# Grove_-_FM_Receiver_v1_0.net
KiCad netlist of a schematic drawn in EAGLE
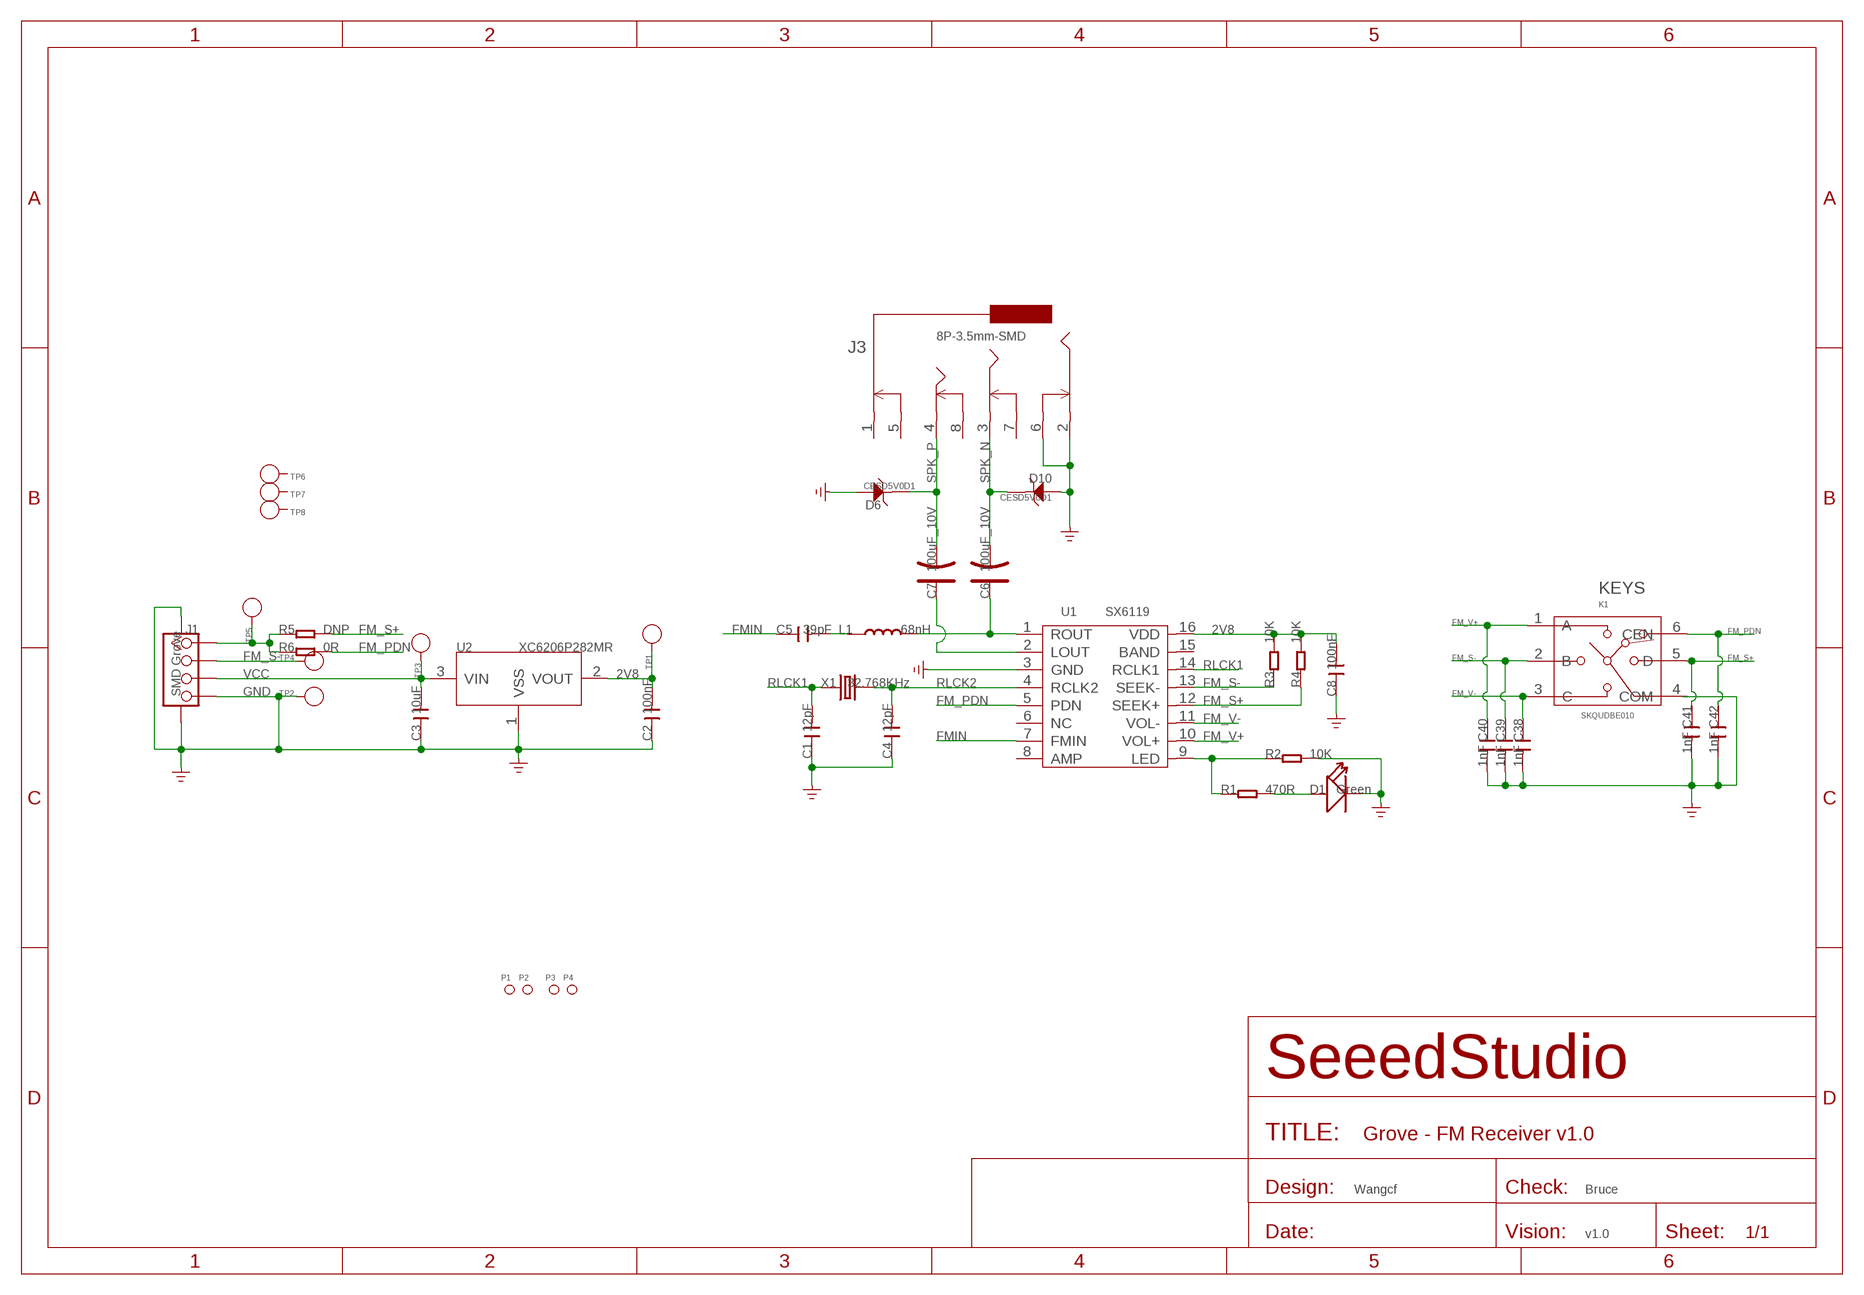
[diagram p0: schematic, sheet 1]

(export (version "E")
  (design (tool "Eeschema 10.0.6"))
  (components
    (comp (ref "C1")
      (value "12pF")
      (footprint "eagle-import:C0603")
      (libsource (lib "eagle-import") (part "C-0603"))
    )
    (comp (ref "C2")
      (value "100nF")
      (footprint "eagle-import:C0603")
      (libsource (lib "eagle-import") (part "C-0603"))
    )
    (comp (ref "C3")
      (value "10uF")
      (footprint "eagle-import:C0805")
      (libsource (lib "eagle-import") (part "C-0805"))
    )
    (comp (ref "C4")
      (value "12pF")
      (footprint "eagle-import:C0603")
      (libsource (lib "eagle-import") (part "C-0603"))
    )
    (comp (ref "C5")
      (value "39pF")
      (footprint "eagle-import:C0603")
      (libsource (lib "eagle-import") (part "C-0603"))
    )
    (comp (ref "C6")
      (value "100uF_10V")
      (footprint "eagle-import:AVX-B")
      (libsource (lib "eagle-import") (part "CAP-AVX-B"))
    )
    (comp (ref "C7")
      (value "100uF_10V")
      (footprint "eagle-import:AVX-B")
      (libsource (lib "eagle-import") (part "CAP-AVX-B"))
    )
    (comp (ref "C8")
      (value "100nF")
      (footprint "eagle-import:C0603")
      (libsource (lib "eagle-import") (part "C-0603"))
    )
    (comp (ref "C38")
      (value "1nF")
      (footprint "eagle-import:C0603")
      (libsource (lib "eagle-import") (part "C-0603"))
    )
    (comp (ref "C39")
      (value "1nF")
      (footprint "eagle-import:C0603")
      (libsource (lib "eagle-import") (part "C-0603"))
    )
    (comp (ref "C40")
      (value "1nF")
      (footprint "eagle-import:C0603")
      (libsource (lib "eagle-import") (part "C-0603"))
    )
    (comp (ref "C41")
      (value "1nF")
      (footprint "eagle-import:C0603")
      (libsource (lib "eagle-import") (part "C-0603"))
    )
    (comp (ref "C42")
      (value "1nF")
      (footprint "eagle-import:C0603")
      (libsource (lib "eagle-import") (part "C-0603"))
    )
    (comp (ref "D1")
      (value "Green")
      (footprint "eagle-import:LED-0603")
      (libsource (lib "eagle-import") (part "LED'0603'"))
    )
    (comp (ref "D6")
      (value "CESD5V0D1")
      (footprint "eagle-import:SOD123-2.7X1.6")
      (libsource (lib "eagle-import") (part "D-ESD"))
    )
    (comp (ref "D10")
      (value "CESD5V0D1")
      (footprint "eagle-import:SOD123-2.7X1.6")
      (libsource (lib "eagle-import") (part "D-ESD"))
    )
    (comp (ref "J1")
      (value "SMD Grove")
      (footprint "eagle-import:4P-SMD-2.0")
      (libsource (lib "eagle-import") (part "TWIG-4P-2.0-SMD-FEMALE-REINFORCE'DD'"))
    )
    (comp (ref "J3")
      (value "8P-3.5mm-SMD")
      (footprint "eagle-import:8P-3.5-SMD")
      (libsource (lib "eagle-import") (part "AUDIO-8P'PJ-3536-L6S'"))
    )
    (comp (ref "K1")
      (value "SKQUDBE010")
      (footprint "eagle-import:6P-10X10X8.6MM")
      (libsource (lib "eagle-import") (part "SKQUDBE010"))
    )
    (comp (ref "L1")
      (value "68nH")
      (footprint "eagle-import:L0603")
      (libsource (lib "eagle-import") (part "L'0603'"))
    )
    (comp (ref "P1")
      (value "PAD-MARK")
      (footprint "eagle-import:ROUND-MARK-1.0")
      (fields (field (name "PARTNO") "DNP"))
      (libsource (lib "eagle-import") (part "PAD-MARK"))
    )
    (comp (ref "P2")
      (value "PAD-MARK")
      (footprint "eagle-import:ROUND-MARK-1.0")
      (fields (field (name "PARTNO") "DNP"))
      (libsource (lib "eagle-import") (part "PAD-MARK"))
    )
    (comp (ref "P3")
      (value "PAD-MARK")
      (footprint "eagle-import:ROUND-MARK-1.0")
      (fields (field (name "PARTNO") "DNP"))
      (libsource (lib "eagle-import") (part "PAD-MARK"))
    )
    (comp (ref "P4")
      (value "PAD-MARK")
      (footprint "eagle-import:ROUND-MARK-1.0")
      (fields (field (name "PARTNO") "DNP"))
      (libsource (lib "eagle-import") (part "PAD-MARK"))
    )
    (comp (ref "R1")
      (value "470R")
      (footprint "eagle-import:R0603")
      (libsource (lib "eagle-import") (part "R-0603"))
    )
    (comp (ref "R2")
      (value "10K")
      (footprint "eagle-import:R0603")
      (libsource (lib "eagle-import") (part "R-0603"))
    )
    (comp (ref "R3")
      (value "10K")
      (footprint "eagle-import:R0603")
      (libsource (lib "eagle-import") (part "R-0603"))
    )
    (comp (ref "R4")
      (value "10K")
      (footprint "eagle-import:R0603")
      (libsource (lib "eagle-import") (part "R-0603"))
    )
    (comp (ref "R5")
      (value "DNP")
      (footprint "eagle-import:R0603")
      (libsource (lib "eagle-import") (part "R-0603"))
    )
    (comp (ref "R6")
      (value "0R")
      (footprint "eagle-import:R0603")
      (libsource (lib "eagle-import") (part "R-0603"))
    )
    (comp (ref "TP1")
      (value "PAD-TEST-POINT'4545'")
      (footprint "eagle-import:TP_4545")
      (fields (field (name "PARTNO") "DNP"))
      (libsource (lib "eagle-import") (part "PAD-TEST-POINT'4545'"))
    )
    (comp (ref "TP2")
      (value "PAD-TEST-POINT'4545'")
      (footprint "eagle-import:TP_4545")
      (fields (field (name "PARTNO") "DNP"))
      (libsource (lib "eagle-import") (part "PAD-TEST-POINT'4545'"))
    )
    (comp (ref "TP3")
      (value "PAD-TEST-POINT'4545'")
      (footprint "eagle-import:TP_4545")
      (fields (field (name "PARTNO") "DNP"))
      (libsource (lib "eagle-import") (part "PAD-TEST-POINT'4545'"))
    )
    (comp (ref "TP4")
      (value "PAD-TEST-POINT'4545'")
      (footprint "eagle-import:TP_4545")
      (fields (field (name "PARTNO") "DNP"))
      (libsource (lib "eagle-import") (part "PAD-TEST-POINT'4545'"))
    )
    (comp (ref "TP5")
      (value "PAD-TEST-POINT'4545'")
      (footprint "eagle-import:TP_4545")
      (fields (field (name "PARTNO") "DNP"))
      (libsource (lib "eagle-import") (part "PAD-TEST-POINT'4545'"))
    )
    (comp (ref "TP6")
      (value "PAD-TEST-POINT'4545'")
      (footprint "eagle-import:TP_4545")
      (fields (field (name "PARTNO") "DNP"))
      (libsource (lib "eagle-import") (part "PAD-TEST-POINT'4545'"))
    )
    (comp (ref "TP7")
      (value "PAD-TEST-POINT'4545'")
      (footprint "eagle-import:TP_4545")
      (fields (field (name "PARTNO") "DNP"))
      (libsource (lib "eagle-import") (part "PAD-TEST-POINT'4545'"))
    )
    (comp (ref "TP8")
      (value "PAD-TEST-POINT'4545'")
      (footprint "eagle-import:TP_4545")
      (fields (field (name "PARTNO") "DNP"))
      (libsource (lib "eagle-import") (part "PAD-TEST-POINT'4545'"))
    )
    (comp (ref "U1")
      (value "SX6119")
      (footprint "eagle-import:SOP16")
      (libsource (lib "eagle-import") (part "SX6119"))
    )
    (comp (ref "U2")
      (value "XC6206P282MR")
      (footprint "eagle-import:SOT23")
      (libsource (lib "eagle-import") (part "XC6206MR"))
    )
    (comp (ref "X1")
      (value "32.768KHz")
      (footprint "eagle-import:2P-SMD-3.2X1.5")
      (libsource (lib "eagle-import") (part "CRYSTAL-3215"))
    )
  )
  (nets
    (net (code "1") (name "/2V8") (class "Default")
      (node (ref "C2") (pin "2") (pinfunction "2_2") (pintype "passive"))
      (node (ref "C8") (pin "2") (pinfunction "2_2") (pintype "passive"))
      (node (ref "R3") (pin "2") (pinfunction "2_2") (pintype "passive"))
      (node (ref "R4") (pin "2") (pinfunction "2_2") (pintype "passive"))
      (node (ref "TP1") (pin "T") (pinfunction "T_T") (pintype "bidirectional"))
      (node (ref "U1") (pin "16") (pinfunction "VDD_16") (pintype "bidirectional"))
      (node (ref "U2") (pin "2") (pinfunction "VOUT_2") (pintype "output"))
    )
    (net (code "2") (name "/FMIN") (class "Default")
      (node (ref "C5") (pin "1") (pinfunction "1_1") (pintype "passive"))
      (node (ref "U1") (pin "7") (pinfunction "FMIN_7") (pintype "bidirectional"))
    )
    (net (code "3") (name "/FM_PDN") (class "Default")
      (node (ref "C42") (pin "1") (pinfunction "1_1") (pintype "passive"))
      (node (ref "K1") (pin "6") (pinfunction "CEN_6") (pintype "bidirectional"))
      (node (ref "R6") (pin "2") (pinfunction "2_2") (pintype "passive"))
      (node (ref "U1") (pin "5") (pinfunction "PDN_5") (pintype "bidirectional"))
    )
    (net (code "4") (name "/FM_S+") (class "Default")
      (node (ref "C41") (pin "1") (pinfunction "1_1") (pintype "passive"))
      (node (ref "K1") (pin "5") (pinfunction "D_5") (pintype "bidirectional"))
      (node (ref "R4") (pin "1") (pinfunction "1_1") (pintype "passive"))
      (node (ref "R5") (pin "2") (pinfunction "2_2") (pintype "passive"))
      (node (ref "U1") (pin "12") (pinfunction "SEEK+_12") (pintype "bidirectional"))
    )
    (net (code "5") (name "/FM_S-") (class "Default")
      (node (ref "C39") (pin "1") (pinfunction "1_1") (pintype "passive"))
      (node (ref "J1") (pin "2") (pinfunction "2_2") (pintype "bidirectional"))
      (node (ref "K1") (pin "2") (pinfunction "B_2") (pintype "bidirectional"))
      (node (ref "R3") (pin "1") (pinfunction "1_1") (pintype "passive"))
      (node (ref "TP4") (pin "T") (pinfunction "T_T") (pintype "bidirectional"))
      (node (ref "U1") (pin "13") (pinfunction "SEEK-_13") (pintype "bidirectional"))
    )
    (net (code "6") (name "/FM_V+") (class "Default")
      (node (ref "C40") (pin "1") (pinfunction "1_1") (pintype "passive"))
      (node (ref "K1") (pin "1") (pinfunction "A_1") (pintype "bidirectional"))
      (node (ref "U1") (pin "10") (pinfunction "VOL+_10") (pintype "bidirectional"))
    )
    (net (code "7") (name "/FM_V-") (class "Default")
      (node (ref "C38") (pin "1") (pinfunction "1_1") (pintype "passive"))
      (node (ref "K1") (pin "3") (pinfunction "C_3") (pintype "bidirectional"))
      (node (ref "U1") (pin "11") (pinfunction "VOL-_11") (pintype "bidirectional"))
    )
    (net (code "8") (name "/RLCK1") (class "Default")
      (node (ref "C1") (pin "2") (pinfunction "2_2") (pintype "passive"))
      (node (ref "U1") (pin "14") (pinfunction "RCLK1_14") (pintype "bidirectional"))
      (node (ref "X1") (pin "1") (pinfunction "1_1") (pintype "passive"))
    )
    (net (code "9") (name "/RLCK2") (class "Default")
      (node (ref "C4") (pin "2") (pinfunction "2_2") (pintype "passive"))
      (node (ref "U1") (pin "4") (pinfunction "RCLK2_4") (pintype "bidirectional"))
      (node (ref "X1") (pin "2") (pinfunction "2_2") (pintype "passive"))
    )
    (net (code "10") (name "/SPK_N") (class "Default")
      (node (ref "C6") (pin "-") (pinfunction "-_-") (pintype "passive"))
      (node (ref "D10") (pin "2") (pinfunction "2_2") (pintype "bidirectional"))
      (node (ref "J3") (pin "3") (pinfunction "3_3") (pintype "bidirectional"))
    )
    (net (code "11") (name "/SPK_P") (class "Default")
      (node (ref "C7") (pin "-") (pinfunction "-_-") (pintype "passive"))
      (node (ref "D6") (pin "2") (pinfunction "2_2") (pintype "bidirectional"))
      (node (ref "J3") (pin "4") (pinfunction "4_4") (pintype "bidirectional"))
    )
    (net (code "12") (name "/VCC") (class "Default")
      (node (ref "C3") (pin "2") (pinfunction "2_2") (pintype "passive"))
      (node (ref "J1") (pin "3") (pinfunction "3_3") (pintype "bidirectional"))
      (node (ref "TP3") (pin "T") (pinfunction "T_T") (pintype "bidirectional"))
      (node (ref "U2") (pin "3") (pinfunction "VIN_3") (pintype "input"))
    )
    (net (code "13") (name "GND_POWER") (class "Default")
      (node (ref "C1") (pin "1") (pinfunction "1_1") (pintype "passive"))
      (node (ref "C2") (pin "1") (pinfunction "1_1") (pintype "passive"))
      (node (ref "C3") (pin "1") (pinfunction "1_1") (pintype "passive"))
      (node (ref "C38") (pin "2") (pinfunction "2_2") (pintype "passive"))
      (node (ref "C39") (pin "2") (pinfunction "2_2") (pintype "passive"))
      (node (ref "C4") (pin "1") (pinfunction "1_1") (pintype "passive"))
      (node (ref "C40") (pin "2") (pinfunction "2_2") (pintype "passive"))
      (node (ref "C41") (pin "2") (pinfunction "2_2") (pintype "passive"))
      (node (ref "C42") (pin "2") (pinfunction "2_2") (pintype "passive"))
      (node (ref "C8") (pin "1") (pinfunction "1_1") (pintype "passive"))
      (node (ref "D1") (pin "-") (pinfunction "-_-") (pintype "passive"))
      (node (ref "D10") (pin "1") (pinfunction "1_1") (pintype "bidirectional"))
      (node (ref "D6") (pin "1") (pinfunction "1_1") (pintype "bidirectional"))
      (node (ref "J1") (pin "4") (pinfunction "4_4") (pintype "bidirectional"))
      (node (ref "J1") (pin "SS1") (pinfunction "SS1_SS1") (pintype "bidirectional"))
      (node (ref "J1") (pin "SS2") (pinfunction "SS2_SS2") (pintype "bidirectional"))
      (node (ref "J3") (pin "2") (pinfunction "2_2") (pintype "bidirectional"))
      (node (ref "J3") (pin "6") (pinfunction "6_6") (pintype "bidirectional"))
      (node (ref "K1") (pin "4") (pinfunction "COM_4") (pintype "bidirectional"))
      (node (ref "R2") (pin "2") (pinfunction "2_2") (pintype "passive"))
      (node (ref "TP2") (pin "T") (pinfunction "T_T") (pintype "bidirectional"))
      (node (ref "U1") (pin "3") (pinfunction "GND_3") (pintype "bidirectional"))
      (node (ref "U2") (pin "1") (pinfunction "VSS_1") (pintype "power_in"))
    )
    (net (code "14") (name "Net-(C5-Pad2)") (class "Default")
      (node (ref "C5") (pin "2") (pinfunction "2_2") (pintype "passive"))
      (node (ref "L1") (pin "1") (pinfunction "1_1") (pintype "passive"))
    )
    (net (code "15") (name "Net-(D1-Pad+)") (class "Default")
      (node (ref "D1") (pin "+") (pinfunction "+_+") (pintype "passive"))
      (node (ref "R1") (pin "2") (pinfunction "2_2") (pintype "passive"))
    )
    (net (code "16") (name "Net-(J1-Pad1)") (class "Default")
      (node (ref "J1") (pin "1") (pinfunction "1_1") (pintype "bidirectional"))
      (node (ref "R5") (pin "1") (pinfunction "1_1") (pintype "passive"))
      (node (ref "R6") (pin "1") (pinfunction "1_1") (pintype "passive"))
      (node (ref "TP5") (pin "T") (pinfunction "T_T") (pintype "bidirectional"))
    )
    (net (code "17") (name "Net-(U1-LED)") (class "Default")
      (node (ref "R1") (pin "1") (pinfunction "1_1") (pintype "passive"))
      (node (ref "R2") (pin "1") (pinfunction "1_1") (pintype "passive"))
      (node (ref "U1") (pin "9") (pinfunction "LED_9") (pintype "bidirectional"))
    )
    (net (code "18") (name "Net-(U1-LOUT)") (class "Default")
      (node (ref "C7") (pin "+") (pinfunction "+_+") (pintype "passive"))
      (node (ref "U1") (pin "2") (pinfunction "LOUT_2") (pintype "bidirectional"))
    )
    (net (code "19") (name "Net-(U1-ROUT)") (class "Default")
      (node (ref "C6") (pin "+") (pinfunction "+_+") (pintype "passive"))
      (node (ref "L1") (pin "2") (pinfunction "2_2") (pintype "passive"))
      (node (ref "U1") (pin "1") (pinfunction "ROUT_1") (pintype "bidirectional"))
    )
    (net (code "20") (name "unconnected-(J3-Pad1)") (class "Default")
      (node (ref "J3") (pin "1") (pinfunction "1_1") (pintype "bidirectional"))
    )
    (net (code "21") (name "unconnected-(J3-Pad5)") (class "Default")
      (node (ref "J3") (pin "5") (pinfunction "5_5") (pintype "bidirectional"))
    )
    (net (code "22") (name "unconnected-(J3-Pad7)") (class "Default")
      (node (ref "J3") (pin "7") (pinfunction "7_7") (pintype "bidirectional"))
    )
    (net (code "23") (name "unconnected-(J3-Pad8)") (class "Default")
      (node (ref "J3") (pin "8") (pinfunction "8_8") (pintype "bidirectional"))
    )
    (net (code "24") (name "unconnected-(TP6-PadT)") (class "Default")
      (node (ref "TP6") (pin "T") (pinfunction "T_T") (pintype "bidirectional"))
    )
    (net (code "25") (name "unconnected-(TP7-PadT)") (class "Default")
      (node (ref "TP7") (pin "T") (pinfunction "T_T") (pintype "bidirectional"))
    )
    (net (code "26") (name "unconnected-(TP8-PadT)") (class "Default")
      (node (ref "TP8") (pin "T") (pinfunction "T_T") (pintype "bidirectional"))
    )
    (net (code "27") (name "unconnected-(U1-AMP-Pad8)") (class "Default")
      (node (ref "U1") (pin "8") (pinfunction "AMP_8") (pintype "bidirectional"))
    )
    (net (code "28") (name "unconnected-(U1-BAND-Pad15)") (class "Default")
      (node (ref "U1") (pin "15") (pinfunction "BAND_15") (pintype "bidirectional"))
    )
    (net (code "29") (name "unconnected-(U1-NC-Pad6)") (class "Default")
      (node (ref "U1") (pin "6") (pinfunction "NC_6") (pintype "bidirectional"))
    )
  )
)
